# FPGA_parts.net
KiCad netlist of a schematic drawn in Altium Designer
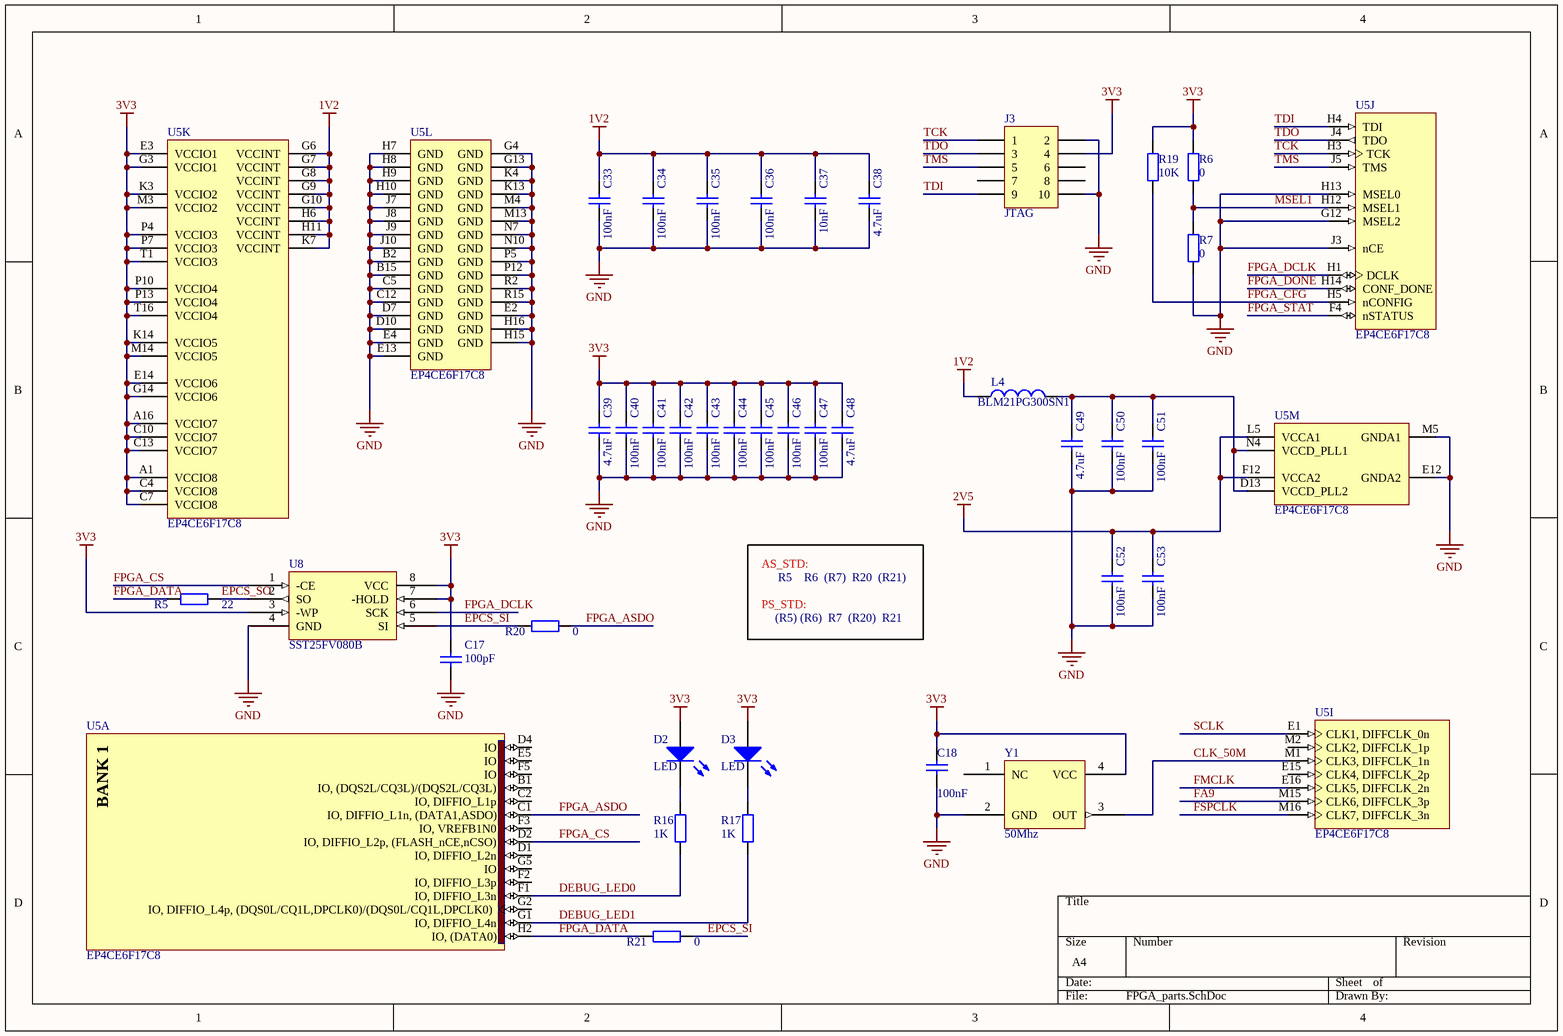
[diagram p0: FPGA_parts.SchDoc]

(export (version "E")
  (design (tool "Eeschema 10.0.6"))
  (components
    (comp (ref "C17")
      (value "100pF")
      (footprint "C0603")
      (description "Capacitor")
      (fields (field (name "PUBLISHER") "Altium Limited"))
      (libsource (lib "Miscellaneous Devices") (part "Cap"))
    )
    (comp (ref "C18")
      (value "100nF")
      (footprint "C0603")
      (description "Capacitor")
      (fields (field (name "PUBLISHER") "Altium Limited"))
      (libsource (lib "Miscellaneous Devices") (part "Cap"))
    )
    (comp (ref "C33")
      (value "100nF")
      (footprint "C0603")
      (description "Capacitor")
      (fields (field (name "PUBLISHER") "Altium Limited"))
      (libsource (lib "Miscellaneous Devices") (part "Cap"))
    )
    (comp (ref "C34")
      (value "100nF")
      (footprint "C0603")
      (description "Capacitor")
      (fields (field (name "PUBLISHER") "Altium Limited"))
      (libsource (lib "Miscellaneous Devices") (part "Cap"))
    )
    (comp (ref "C35")
      (value "100nF")
      (footprint "C0603")
      (description "Capacitor")
      (fields (field (name "PUBLISHER") "Altium Limited"))
      (libsource (lib "Miscellaneous Devices") (part "Cap"))
    )
    (comp (ref "C36")
      (value "100nF")
      (footprint "C0603")
      (description "Capacitor")
      (fields (field (name "PUBLISHER") "Altium Limited"))
      (libsource (lib "Miscellaneous Devices") (part "Cap"))
    )
    (comp (ref "C37")
      (value "10nF")
      (footprint "C0603")
      (description "Capacitor")
      (fields (field (name "PUBLISHER") "Altium Limited"))
      (libsource (lib "Miscellaneous Devices") (part "Cap"))
    )
    (comp (ref "C38")
      (value "4.7uF")
      (footprint "C0603")
      (description "Capacitor")
      (fields (field (name "PUBLISHER") "Altium Limited"))
      (libsource (lib "Miscellaneous Devices") (part "Cap"))
    )
    (comp (ref "C39")
      (value "4.7uF")
      (footprint "C0603")
      (description "Capacitor")
      (fields (field (name "PUBLISHER") "Altium Limited"))
      (libsource (lib "Miscellaneous Devices") (part "Cap"))
    )
    (comp (ref "C40")
      (value "100nF")
      (footprint "C0603")
      (description "Capacitor")
      (fields (field (name "PUBLISHER") "Altium Limited"))
      (libsource (lib "Miscellaneous Devices") (part "Cap"))
    )
    (comp (ref "C41")
      (value "100nF")
      (footprint "C0603")
      (description "Capacitor")
      (fields (field (name "PUBLISHER") "Altium Limited"))
      (libsource (lib "Miscellaneous Devices") (part "Cap"))
    )
    (comp (ref "C42")
      (value "100nF")
      (footprint "C0603")
      (description "Capacitor")
      (fields (field (name "PUBLISHER") "Altium Limited"))
      (libsource (lib "Miscellaneous Devices") (part "Cap"))
    )
    (comp (ref "C43")
      (value "100nF")
      (footprint "C0603")
      (description "Capacitor")
      (fields (field (name "PUBLISHER") "Altium Limited"))
      (libsource (lib "Miscellaneous Devices") (part "Cap"))
    )
    (comp (ref "C44")
      (value "100nF")
      (footprint "C0603")
      (description "Capacitor")
      (fields (field (name "PUBLISHER") "Altium Limited"))
      (libsource (lib "Miscellaneous Devices") (part "Cap"))
    )
    (comp (ref "C45")
      (value "100nF")
      (footprint "C0603")
      (description "Capacitor")
      (fields (field (name "PUBLISHER") "Altium Limited"))
      (libsource (lib "Miscellaneous Devices") (part "Cap"))
    )
    (comp (ref "C46")
      (value "100nF")
      (footprint "C0603")
      (description "Capacitor")
      (fields (field (name "PUBLISHER") "Altium Limited"))
      (libsource (lib "Miscellaneous Devices") (part "Cap"))
    )
    (comp (ref "C47")
      (value "100nF")
      (footprint "C0603")
      (description "Capacitor")
      (fields (field (name "PUBLISHER") "Altium Limited"))
      (libsource (lib "Miscellaneous Devices") (part "Cap"))
    )
    (comp (ref "C48")
      (value "4.7uF")
      (footprint "C0603")
      (description "Capacitor")
      (fields (field (name "PUBLISHER") "Altium Limited"))
      (libsource (lib "Miscellaneous Devices") (part "Cap"))
    )
    (comp (ref "C49")
      (value "4.7uF")
      (footprint "C0603")
      (description "Capacitor")
      (fields (field (name "PUBLISHER") "Altium Limited"))
      (libsource (lib "Miscellaneous Devices") (part "Cap"))
    )
    (comp (ref "C50")
      (value "100nF")
      (footprint "C0603")
      (description "Capacitor")
      (fields (field (name "PUBLISHER") "Altium Limited"))
      (libsource (lib "Miscellaneous Devices") (part "Cap"))
    )
    (comp (ref "C51")
      (value "100nF")
      (footprint "C0603")
      (description "Capacitor")
      (fields (field (name "PUBLISHER") "Altium Limited"))
      (libsource (lib "Miscellaneous Devices") (part "Cap"))
    )
    (comp (ref "C52")
      (value "100nF")
      (footprint "C0603")
      (description "Capacitor")
      (fields (field (name "PUBLISHER") "Altium Limited"))
      (libsource (lib "Miscellaneous Devices") (part "Cap"))
    )
    (comp (ref "C53")
      (value "100nF")
      (footprint "C0603")
      (description "Capacitor")
      (fields (field (name "PUBLISHER") "Altium Limited"))
      (libsource (lib "Miscellaneous Devices") (part "Cap"))
    )
    (comp (ref "D2")
      (value "LED")
      (footprint "D0603")
      (description "Typical RED GaAs LED")
      (fields (field (name "PUBLISHER") "Altium Limited"))
      (libsource (lib "PCB_Project1") (part "LED1"))
    )
    (comp (ref "D3")
      (value "LED")
      (footprint "D0603")
      (description "Typical RED GaAs LED")
      (fields (field (name "PUBLISHER") "Altium Limited"))
      (libsource (lib "PCB_Project1") (part "LED1"))
    )
    (comp (ref "J3")
      (value "JTAG")
      (footprint "HDR2X5")
      (description "Header, 5-Pin, Dual row")
      (fields (field (name "PUBLISHER") "Altium Limited"))
      (libsource (lib "Miscellaneous Connectors") (part "Header 5X2"))
    )
    (comp (ref "L4")
      (value "BLM21PG300SN1")
      (footprint "R0805")
      (description "Inductor")
      (fields (field (name "PUBLISHER") "Altium Limited"))
      (libsource (lib "Miscellaneous Devices") (part "Inductor"))
    )
    (comp (ref "R5")
      (value "22")
      (footprint "R0603")
      (description "Resistor")
      (fields (field (name "PUBLISHER") "Altium Limited"))
      (libsource (lib "") (part "Res2_1"))
    )
    (comp (ref "R6")
      (value "0")
      (footprint "R0603")
      (description "Resistor")
      (fields (field (name "PUBLISHER") "Altium Limited"))
      (libsource (lib "Miscellaneous Devices") (part "Res2"))
    )
    (comp (ref "R7")
      (value "0")
      (footprint "R0603")
      (description "Resistor")
      (fields (field (name "PUBLISHER") "Altium Limited"))
      (libsource (lib "Miscellaneous Devices") (part "Res2"))
    )
    (comp (ref "R16")
      (value "1K")
      (footprint "R0603")
      (description "Resistor")
      (fields (field (name "PUBLISHER") "Altium Limited"))
      (libsource (lib "Miscellaneous Devices") (part "Res2"))
    )
    (comp (ref "R17")
      (value "1K")
      (footprint "R0603")
      (description "Resistor")
      (fields (field (name "PUBLISHER") "Altium Limited"))
      (libsource (lib "Miscellaneous Devices") (part "Res2"))
    )
    (comp (ref "R19")
      (value "10K")
      (footprint "R0603")
      (description "Resistor")
      (fields (field (name "PUBLISHER") "Altium Limited"))
      (libsource (lib "Miscellaneous Devices") (part "Res2"))
    )
    (comp (ref "R20")
      (value "0")
      (footprint "R0603")
      (description "Resistor")
      (fields (field (name "PUBLISHER") "Altium Limited"))
      (libsource (lib "") (part "Res2_1"))
    )
    (comp (ref "R21")
      (value "0")
      (footprint "R0603")
      (description "Resistor")
      (fields (field (name "PUBLISHER") "Altium Limited"))
      (libsource (lib "") (part "Res2_1"))
    )
    (comp (ref "U5")
      (value "EP4CE6F17C8")
      (footprint "FBGA256")
      (fields (field (name "PUBLISHER") "Altium Limited"))
      (libsource (lib "Altera Cyclone IV E") (part "EP4CE6F17C8"))
    )
    (comp (ref "U8")
      (value "SST25FV080B")
      (footprint "SOIC-8")
      (libsource (lib "JL_SCH") (part "SST25FV080B"))
    )
    (comp (ref "Y1") (value "50Mhz") (footprint "OSC_5032") (libsource (lib "JL_SCH") (part "JZSMD5X7")))
  )
  (nets
    (net (code "1") (name "/CLK_50M") (class "Default")
      (node (ref "U5") (pin "M1") (pinfunction "CLK3,_DIFFCLK_1n_M1") (pintype "input"))
      (node (ref "Y1") (pin "3") (pinfunction "OUT_3") (pintype "output"))
    )
    (net (code "2") (name "/DEBUG_LED0") (class "Default")
      (node (ref "R16") (pin "1") (pinfunction "1_1") (pintype "passive"))
      (node (ref "U5") (pin "F1") (pinfunction "IO,_DIFFIO_L3n_F1") (pintype "bidirectional"))
    )
    (net (code "3") (name "/DEBUG_LED1") (class "Default")
      (node (ref "R17") (pin "1") (pinfunction "1_1") (pintype "passive"))
      (node (ref "U5") (pin "G1") (pinfunction "IO,_DIFFIO_L4n_G1") (pintype "bidirectional"))
    )
    (net (code "4") (name "/EPCS_SI") (class "Default")
      (node (ref "R20") (pin "1") (pinfunction "1_1") (pintype "passive"))
      (node (ref "R21") (pin "2") (pinfunction "2_2") (pintype "passive"))
      (node (ref "U8") (pin "5") (pinfunction "SI_5") (pintype "input"))
    )
    (net (code "5") (name "/EPCS_SO") (class "Default")
      (node (ref "R5") (pin "2") (pinfunction "2_2") (pintype "passive"))
      (node (ref "U8") (pin "2") (pinfunction "SO_2") (pintype "output"))
    )
    (net (code "6") (name "/FA9") (class "Default")
      (node (ref "U5") (pin "M15") (pinfunction "CLK6,_DIFFCLK_3p_M15") (pintype "input"))
    )
    (net (code "7") (name "/FMCLK") (class "Default")
      (node (ref "U5") (pin "E16") (pinfunction "CLK5,_DIFFCLK_2n_E16") (pintype "input"))
    )
    (net (code "8") (name "/FPGA_ASDO") (class "Default")
      (node (ref "R20") (pin "2") (pinfunction "2_2") (pintype "passive"))
      (node (ref "U5") (pin "C1") (pinfunction "IO,_DIFFIO_L1n,_(DATA1,ASDO)_C1") (pintype "bidirectional"))
    )
    (net (code "9") (name "/FPGA_CFG") (class "Default")
      (node (ref "R19") (pin "1") (pinfunction "1_1") (pintype "passive"))
      (node (ref "U5") (pin "H5") (pinfunction "nCONFIG_H5") (pintype "input"))
    )
    (net (code "10") (name "/FPGA_CS") (class "Default")
      (node (ref "U5") (pin "D2") (pinfunction "IO,_DIFFIO_L2p,_(FLASH_nCE,nCSO)_D2") (pintype "bidirectional"))
      (node (ref "U8") (pin "1") (pinfunction "-CE_1") (pintype "input"))
    )
    (net (code "11") (name "/FPGA_DATA") (class "Default")
      (node (ref "R21") (pin "1") (pinfunction "1_1") (pintype "passive"))
      (node (ref "R5") (pin "1") (pinfunction "1_1") (pintype "passive"))
      (node (ref "U5") (pin "H2") (pinfunction "IO,_(DATA0)_H2") (pintype "bidirectional"))
    )
    (net (code "12") (name "/FPGA_DCLK") (class "Default")
      (node (ref "U5") (pin "H1") (pinfunction "DCLK_H1") (pintype "bidirectional"))
      (node (ref "U8") (pin "6") (pinfunction "SCK_6") (pintype "input"))
    )
    (net (code "13") (name "/FPGA_DONE") (class "Default")
      (node (ref "U5") (pin "H14") (pinfunction "CONF_DONE_H14") (pintype "bidirectional"))
    )
    (net (code "14") (name "/FPGA_STAT") (class "Default")
      (node (ref "U5") (pin "F4") (pinfunction "nSTATUS_F4") (pintype "bidirectional"))
    )
    (net (code "15") (name "/FSPCLK") (class "Default")
      (node (ref "U5") (pin "M16") (pinfunction "CLK7,_DIFFCLK_3n_M16") (pintype "input"))
    )
    (net (code "16") (name "/MSEL1") (class "Default")
      (node (ref "R6") (pin "1") (pinfunction "1_1") (pintype "passive"))
      (node (ref "R7") (pin "2") (pinfunction "2_2") (pintype "passive"))
      (node (ref "U5") (pin "H12") (pinfunction "MSEL1_H12") (pintype "input"))
    )
    (net (code "17") (name "/SCLK") (class "Default")
      (node (ref "U5") (pin "E1") (pinfunction "CLK1,_DIFFCLK_0n_E1") (pintype "input"))
    )
    (net (code "18") (name "/TCK") (class "Default")
      (node (ref "J3") (pin "1") (pinfunction "1_1") (pintype "passive"))
      (node (ref "U5") (pin "H3") (pinfunction "TCK_H3") (pintype "input"))
    )
    (net (code "19") (name "/TDI") (class "Default")
      (node (ref "J3") (pin "9") (pinfunction "9_9") (pintype "passive"))
      (node (ref "U5") (pin "H4") (pinfunction "TDI_H4") (pintype "input"))
    )
    (net (code "20") (name "/TDO") (class "Default")
      (node (ref "J3") (pin "3") (pinfunction "3_3") (pintype "passive"))
      (node (ref "U5") (pin "J4") (pinfunction "TDO_J4") (pintype "output"))
    )
    (net (code "21") (name "/TMS") (class "Default")
      (node (ref "J3") (pin "5") (pinfunction "5_5") (pintype "passive"))
      (node (ref "U5") (pin "J5") (pinfunction "TMS_J5") (pintype "input"))
    )
    (net (code "22") (name "1V2") (class "Default")
      (node (ref "C33") (pin "2") (pinfunction "2_2") (pintype "passive"))
      (node (ref "C34") (pin "2") (pinfunction "2_2") (pintype "passive"))
      (node (ref "C35") (pin "2") (pinfunction "2_2") (pintype "passive"))
      (node (ref "C36") (pin "2") (pinfunction "2_2") (pintype "passive"))
      (node (ref "C37") (pin "2") (pinfunction "2_2") (pintype "passive"))
      (node (ref "C38") (pin "2") (pinfunction "2_2") (pintype "passive"))
      (node (ref "L4") (pin "1") (pinfunction "1_1") (pintype "passive"))
      (node (ref "U5") (pin "G10") (pinfunction "VCCINT_G10") (pintype "power_in"))
      (node (ref "U5") (pin "G6") (pinfunction "VCCINT_G6") (pintype "power_in"))
      (node (ref "U5") (pin "G7") (pinfunction "VCCINT_G7") (pintype "power_in"))
      (node (ref "U5") (pin "G8") (pinfunction "VCCINT_G8") (pintype "power_in"))
      (node (ref "U5") (pin "G9") (pinfunction "VCCINT_G9") (pintype "power_in"))
      (node (ref "U5") (pin "H11") (pinfunction "VCCINT_H11") (pintype "power_in"))
      (node (ref "U5") (pin "H6") (pinfunction "VCCINT_H6") (pintype "power_in"))
      (node (ref "U5") (pin "K7") (pinfunction "VCCINT_K7") (pintype "power_in"))
    )
    (net (code "23") (name "2V5") (class "Default")
      (node (ref "C52") (pin "2") (pinfunction "2_2") (pintype "passive"))
      (node (ref "C53") (pin "2") (pinfunction "2_2") (pintype "passive"))
      (node (ref "U5") (pin "F12") (pinfunction "VCCA2_F12") (pintype "power_in"))
      (node (ref "U5") (pin "L5") (pinfunction "VCCA1_L5") (pintype "power_in"))
    )
    (net (code "24") (name "3V3") (class "Default")
      (node (ref "C17") (pin "2") (pinfunction "2_2") (pintype "passive"))
      (node (ref "C18") (pin "2") (pinfunction "2_2") (pintype "passive"))
      (node (ref "C39") (pin "2") (pinfunction "2_2") (pintype "passive"))
      (node (ref "C40") (pin "2") (pinfunction "2_2") (pintype "passive"))
      (node (ref "C41") (pin "2") (pinfunction "2_2") (pintype "passive"))
      (node (ref "C42") (pin "2") (pinfunction "2_2") (pintype "passive"))
      (node (ref "C43") (pin "2") (pinfunction "2_2") (pintype "passive"))
      (node (ref "C44") (pin "2") (pinfunction "2_2") (pintype "passive"))
      (node (ref "C45") (pin "2") (pinfunction "2_2") (pintype "passive"))
      (node (ref "C46") (pin "2") (pinfunction "2_2") (pintype "passive"))
      (node (ref "C47") (pin "2") (pinfunction "2_2") (pintype "passive"))
      (node (ref "C48") (pin "2") (pinfunction "2_2") (pintype "passive"))
      (node (ref "D2") (pin "1") (pinfunction "1_1") (pintype "passive"))
      (node (ref "D3") (pin "1") (pinfunction "1_1") (pintype "passive"))
      (node (ref "J3") (pin "4") (pinfunction "4_4") (pintype "passive"))
      (node (ref "R19") (pin "2") (pinfunction "2_2") (pintype "passive"))
      (node (ref "R6") (pin "2") (pinfunction "2_2") (pintype "passive"))
      (node (ref "U5") (pin "A1") (pinfunction "VCCIO8_A1") (pintype "power_in"))
      (node (ref "U5") (pin "A16") (pinfunction "VCCIO7_A16") (pintype "power_in"))
      (node (ref "U5") (pin "C10") (pinfunction "VCCIO7_C10") (pintype "power_in"))
      (node (ref "U5") (pin "C13") (pinfunction "VCCIO7_C13") (pintype "power_in"))
      (node (ref "U5") (pin "C4") (pinfunction "VCCIO8_C4") (pintype "power_in"))
      (node (ref "U5") (pin "C7") (pinfunction "VCCIO8_C7") (pintype "power_in"))
      (node (ref "U5") (pin "E14") (pinfunction "VCCIO6_E14") (pintype "power_in"))
      (node (ref "U5") (pin "E3") (pinfunction "VCCIO1_E3") (pintype "power_in"))
      (node (ref "U5") (pin "G14") (pinfunction "VCCIO6_G14") (pintype "power_in"))
      (node (ref "U5") (pin "G3") (pinfunction "VCCIO1_G3") (pintype "power_in"))
      (node (ref "U5") (pin "K14") (pinfunction "VCCIO5_K14") (pintype "power_in"))
      (node (ref "U5") (pin "K3") (pinfunction "VCCIO2_K3") (pintype "power_in"))
      (node (ref "U5") (pin "M14") (pinfunction "VCCIO5_M14") (pintype "power_in"))
      (node (ref "U5") (pin "M3") (pinfunction "VCCIO2_M3") (pintype "power_in"))
      (node (ref "U5") (pin "P10") (pinfunction "VCCIO4_P10") (pintype "power_in"))
      (node (ref "U5") (pin "P13") (pinfunction "VCCIO4_P13") (pintype "power_in"))
      (node (ref "U5") (pin "P4") (pinfunction "VCCIO3_P4") (pintype "power_in"))
      (node (ref "U5") (pin "P7") (pinfunction "VCCIO3_P7") (pintype "power_in"))
      (node (ref "U5") (pin "T1") (pinfunction "VCCIO3_T1") (pintype "power_in"))
      (node (ref "U5") (pin "T16") (pinfunction "VCCIO4_T16") (pintype "power_in"))
      (node (ref "U8") (pin "3") (pinfunction "-WP_3") (pintype "input"))
      (node (ref "U8") (pin "7") (pinfunction "-HOLD_7") (pintype "input"))
      (node (ref "U8") (pin "8") (pinfunction "VCC_8") (pintype "power_in"))
      (node (ref "Y1") (pin "4") (pinfunction "VCC_4") (pintype "power_in"))
    )
    (net (code "25") (name "GND") (class "Default")
      (node (ref "C17") (pin "1") (pinfunction "1_1") (pintype "passive"))
      (node (ref "C18") (pin "1") (pinfunction "1_1") (pintype "passive"))
      (node (ref "C33") (pin "1") (pinfunction "1_1") (pintype "passive"))
      (node (ref "C34") (pin "1") (pinfunction "1_1") (pintype "passive"))
      (node (ref "C35") (pin "1") (pinfunction "1_1") (pintype "passive"))
      (node (ref "C36") (pin "1") (pinfunction "1_1") (pintype "passive"))
      (node (ref "C37") (pin "1") (pinfunction "1_1") (pintype "passive"))
      (node (ref "C38") (pin "1") (pinfunction "1_1") (pintype "passive"))
      (node (ref "C39") (pin "1") (pinfunction "1_1") (pintype "passive"))
      (node (ref "C40") (pin "1") (pinfunction "1_1") (pintype "passive"))
      (node (ref "C41") (pin "1") (pinfunction "1_1") (pintype "passive"))
      (node (ref "C42") (pin "1") (pinfunction "1_1") (pintype "passive"))
      (node (ref "C43") (pin "1") (pinfunction "1_1") (pintype "passive"))
      (node (ref "C44") (pin "1") (pinfunction "1_1") (pintype "passive"))
      (node (ref "C45") (pin "1") (pinfunction "1_1") (pintype "passive"))
      (node (ref "C46") (pin "1") (pinfunction "1_1") (pintype "passive"))
      (node (ref "C47") (pin "1") (pinfunction "1_1") (pintype "passive"))
      (node (ref "C48") (pin "1") (pinfunction "1_1") (pintype "passive"))
      (node (ref "C49") (pin "1") (pinfunction "1_1") (pintype "passive"))
      (node (ref "C50") (pin "1") (pinfunction "1_1") (pintype "passive"))
      (node (ref "C51") (pin "1") (pinfunction "1_1") (pintype "passive"))
      (node (ref "C52") (pin "1") (pinfunction "1_1") (pintype "passive"))
      (node (ref "C53") (pin "1") (pinfunction "1_1") (pintype "passive"))
      (node (ref "J3") (pin "10") (pinfunction "10_10") (pintype "passive"))
      (node (ref "J3") (pin "2") (pinfunction "2_2") (pintype "passive"))
      (node (ref "R7") (pin "1") (pinfunction "1_1") (pintype "passive"))
      (node (ref "U5") (pin "B15") (pinfunction "GND_B15") (pintype "power_in"))
      (node (ref "U5") (pin "B2") (pinfunction "GND_B2") (pintype "power_in"))
      (node (ref "U5") (pin "C12") (pinfunction "GND_C12") (pintype "power_in"))
      (node (ref "U5") (pin "C5") (pinfunction "GND_C5") (pintype "power_in"))
      (node (ref "U5") (pin "D10") (pinfunction "GND_D10") (pintype "power_in"))
      (node (ref "U5") (pin "D7") (pinfunction "GND_D7") (pintype "power_in"))
      (node (ref "U5") (pin "E12") (pinfunction "GNDA2_E12") (pintype "power_in"))
      (node (ref "U5") (pin "E13") (pinfunction "GND_E13") (pintype "power_in"))
      (node (ref "U5") (pin "E2") (pinfunction "GND_E2") (pintype "power_in"))
      (node (ref "U5") (pin "E4") (pinfunction "GND_E4") (pintype "power_in"))
      (node (ref "U5") (pin "G12") (pinfunction "MSEL2_G12") (pintype "input"))
      (node (ref "U5") (pin "G13") (pinfunction "GND_G13") (pintype "power_in"))
      (node (ref "U5") (pin "G4") (pinfunction "GND_G4") (pintype "power_in"))
      (node (ref "U5") (pin "H10") (pinfunction "GND_H10") (pintype "power_in"))
      (node (ref "U5") (pin "H13") (pinfunction "MSEL0_H13") (pintype "input"))
      (node (ref "U5") (pin "H15") (pinfunction "GND_H15") (pintype "power_in"))
      (node (ref "U5") (pin "H16") (pinfunction "GND_H16") (pintype "power_in"))
      (node (ref "U5") (pin "H7") (pinfunction "GND_H7") (pintype "power_in"))
      (node (ref "U5") (pin "H8") (pinfunction "GND_H8") (pintype "power_in"))
      (node (ref "U5") (pin "H9") (pinfunction "GND_H9") (pintype "power_in"))
      (node (ref "U5") (pin "J10") (pinfunction "GND_J10") (pintype "power_in"))
      (node (ref "U5") (pin "J3") (pinfunction "nCE_J3") (pintype "input"))
      (node (ref "U5") (pin "J7") (pinfunction "GND_J7") (pintype "power_in"))
      (node (ref "U5") (pin "J8") (pinfunction "GND_J8") (pintype "power_in"))
      (node (ref "U5") (pin "J9") (pinfunction "GND_J9") (pintype "power_in"))
      (node (ref "U5") (pin "K13") (pinfunction "GND_K13") (pintype "power_in"))
      (node (ref "U5") (pin "K4") (pinfunction "GND_K4") (pintype "power_in"))
      (node (ref "U5") (pin "M13") (pinfunction "GND_M13") (pintype "power_in"))
      (node (ref "U5") (pin "M4") (pinfunction "GND_M4") (pintype "power_in"))
      (node (ref "U5") (pin "M5") (pinfunction "GNDA1_M5") (pintype "power_in"))
      (node (ref "U5") (pin "N10") (pinfunction "GND_N10") (pintype "power_in"))
      (node (ref "U5") (pin "N7") (pinfunction "GND_N7") (pintype "power_in"))
      (node (ref "U5") (pin "P12") (pinfunction "GND_P12") (pintype "power_in"))
      (node (ref "U5") (pin "P5") (pinfunction "GND_P5") (pintype "power_in"))
      (node (ref "U5") (pin "R15") (pinfunction "GND_R15") (pintype "power_in"))
      (node (ref "U5") (pin "R2") (pinfunction "GND_R2") (pintype "power_in"))
      (node (ref "U8") (pin "4") (pinfunction "GND_4") (pintype "power_in"))
      (node (ref "Y1") (pin "2") (pinfunction "GND_2") (pintype "power_in"))
    )
    (net (code "26") (name "Net-(D2-Pad2)") (class "Default")
      (node (ref "D2") (pin "2") (pinfunction "2_2") (pintype "passive"))
      (node (ref "R16") (pin "2") (pinfunction "2_2") (pintype "passive"))
    )
    (net (code "27") (name "Net-(D3-Pad2)") (class "Default")
      (node (ref "D3") (pin "2") (pinfunction "2_2") (pintype "passive"))
      (node (ref "R17") (pin "2") (pinfunction "2_2") (pintype "passive"))
    )
    (net (code "28") (name "Net-(U5M-VCCD_PLL1)") (class "Default")
      (node (ref "C49") (pin "2") (pinfunction "2_2") (pintype "passive"))
      (node (ref "C50") (pin "2") (pinfunction "2_2") (pintype "passive"))
      (node (ref "C51") (pin "2") (pinfunction "2_2") (pintype "passive"))
      (node (ref "L4") (pin "2") (pinfunction "2_2") (pintype "passive"))
      (node (ref "U5") (pin "D13") (pinfunction "VCCD_PLL2_D13") (pintype "power_in"))
      (node (ref "U5") (pin "N4") (pinfunction "VCCD_PLL1_N4") (pintype "power_in"))
    )
    (net (code "29") (name "unconnected-(J3-Pad6)") (class "Default")
      (node (ref "J3") (pin "6") (pinfunction "6_6") (pintype "passive"))
    )
    (net (code "30") (name "unconnected-(J3-Pad7)") (class "Default")
      (node (ref "J3") (pin "7") (pinfunction "7_7") (pintype "passive"))
    )
    (net (code "31") (name "unconnected-(J3-Pad8)") (class "Default")
      (node (ref "J3") (pin "8") (pinfunction "8_8") (pintype "passive"))
    )
    (net (code "32") (name "unconnected-(U5A-IO,_(DQS2L{slash}CQ3L){slash}(DQS2L{slash}CQ3L)-PadB1)") (class "Default")
      (node (ref "U5") (pin "B1") (pinfunction "IO,_(DQS2L/CQ3L)/(DQS2L/CQ3L)_B1") (pintype "bidirectional"))
    )
    (net (code "33") (name "unconnected-(U5A-IO,_DIFFIO_L1p-PadC2)") (class "Default")
      (node (ref "U5") (pin "C2") (pinfunction "IO,_DIFFIO_L1p_C2") (pintype "bidirectional"))
    )
    (net (code "34") (name "unconnected-(U5A-IO,_DIFFIO_L2n-PadD1)") (class "Default")
      (node (ref "U5") (pin "D1") (pinfunction "IO,_DIFFIO_L2n_D1") (pintype "bidirectional"))
    )
    (net (code "35") (name "unconnected-(U5A-IO,_DIFFIO_L3p-PadF2)") (class "Default")
      (node (ref "U5") (pin "F2") (pinfunction "IO,_DIFFIO_L3p_F2") (pintype "bidirectional"))
    )
    (net (code "36") (name "unconnected-(U5A-IO,_DIFFIO_L4p,_(DQS0L{slash}CQ1L,DPCLK0){slash}(DQS0L{slash}CQ1L,DPCLK0)-PadG2)") (class "Default")
      (node (ref "U5") (pin "G2") (pinfunction "IO,_DIFFIO_L4p,_(DQS0L/CQ1L,DPCLK0)/(DQS0L/CQ1L,DPCLK0)_G2") (pintype "bidirectional"))
    )
    (net (code "37") (name "unconnected-(U5A-IO,_VREFB1N0-PadF3)") (class "Default")
      (node (ref "U5") (pin "F3") (pinfunction "IO,_VREFB1N0_F3") (pintype "bidirectional"))
    )
    (net (code "38") (name "unconnected-(U5A-IO-PadD4)") (class "Default")
      (node (ref "U5") (pin "D4") (pinfunction "IO_D4") (pintype "bidirectional"))
    )
    (net (code "39") (name "unconnected-(U5A-IO-PadE5)") (class "Default")
      (node (ref "U5") (pin "E5") (pinfunction "IO_E5") (pintype "bidirectional"))
    )
    (net (code "40") (name "unconnected-(U5A-IO-PadF5)") (class "Default")
      (node (ref "U5") (pin "F5") (pinfunction "IO_F5") (pintype "bidirectional"))
    )
    (net (code "41") (name "unconnected-(U5A-IO-PadG5)") (class "Default")
      (node (ref "U5") (pin "G5") (pinfunction "IO_G5") (pintype "bidirectional"))
    )
    (net (code "42") (name "unconnected-(U5I-CLK2,_DIFFCLK_1p-PadM2)") (class "Default")
      (node (ref "U5") (pin "M2") (pinfunction "CLK2,_DIFFCLK_1p_M2") (pintype "input"))
    )
    (net (code "43") (name "unconnected-(U5I-CLK4,_DIFFCLK_2p-PadE15)") (class "Default")
      (node (ref "U5") (pin "E15") (pinfunction "CLK4,_DIFFCLK_2p_E15") (pintype "input"))
    )
    (net (code "44") (name "unconnected-(Y1-NC-Pad1)") (class "Default")
      (node (ref "Y1") (pin "1") (pinfunction "NC_1") (pintype "passive"))
    )
  )
)
